# Top.net
KiCad netlist of a schematic drawn in Altium Designer
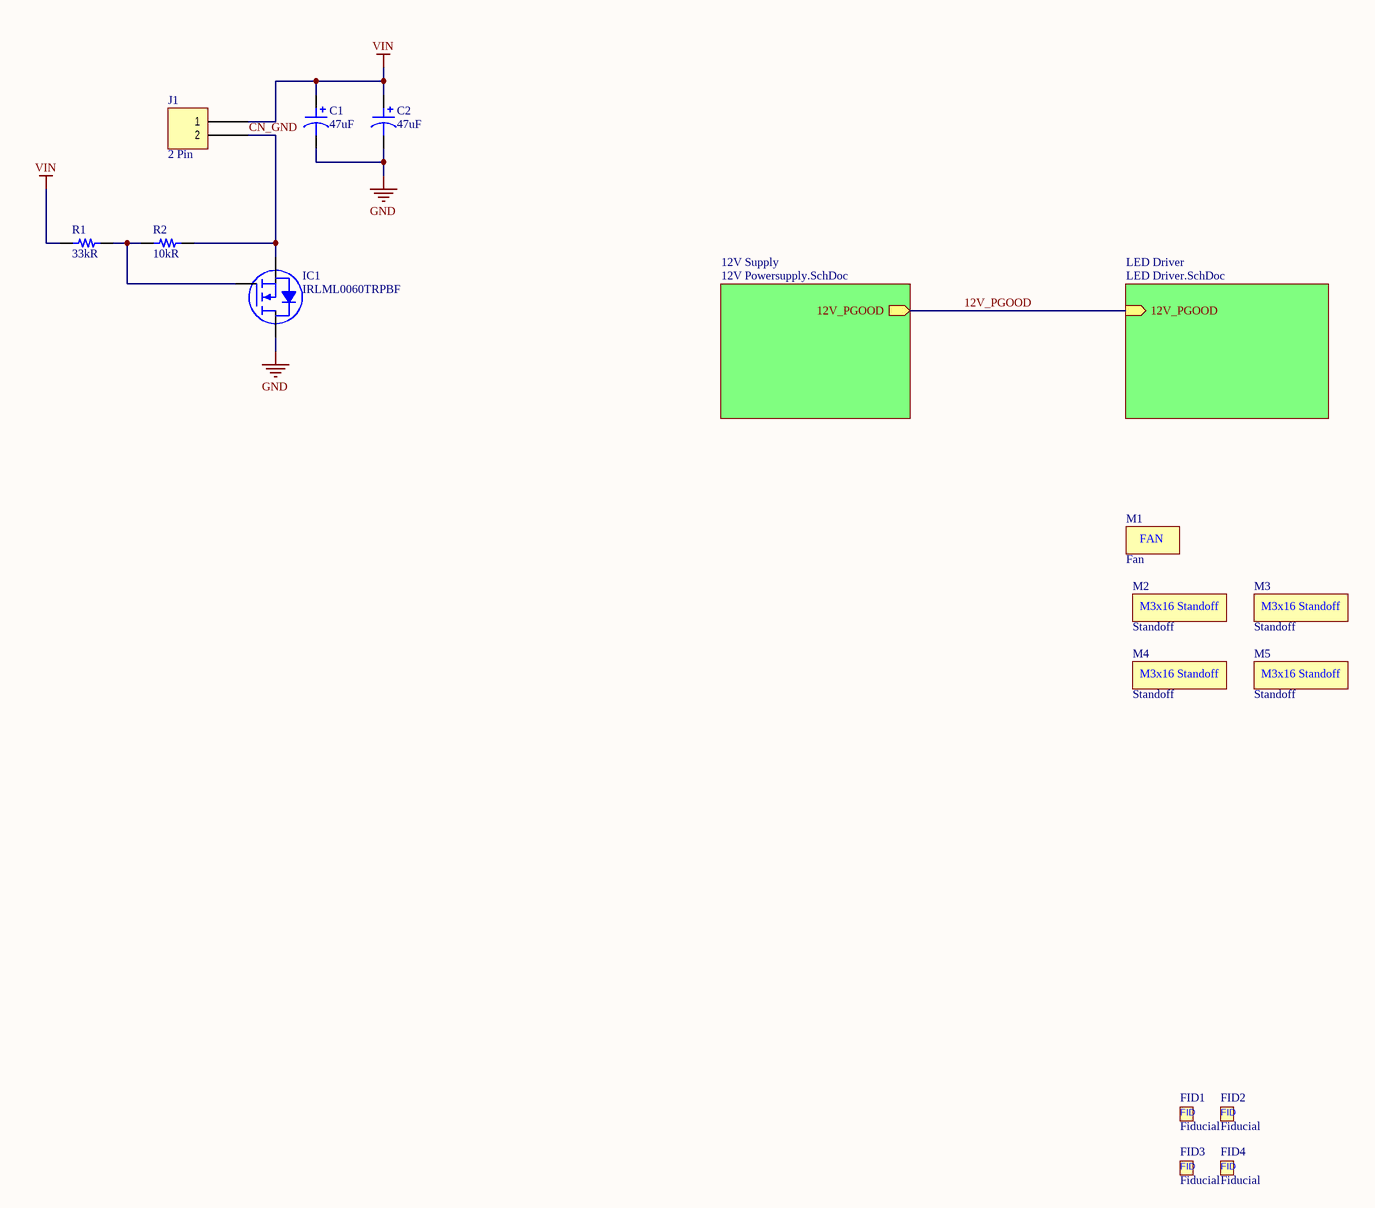
[diagram p0: Top.SchDoc]

(export (version "E")
  (design (tool "Eeschema 10.0.6"))
  (components
    (comp (ref "C1")
      (value "47uF")
      (footprint "CAP ALUM 8.3MM")
      (description "Aluminum Electrolytic Capacitors - SMD 63volts 47uF 20% 85C 8X10")
      (fields (field (name "TOLERANCE") "20%"))
      (libsource (lib "SCH - PASSIVES - POLARISED CAPACITOR") (part "Polarised Capacitor"))
    )
    (comp (ref "C2")
      (value "47uF")
      (footprint "CAP ALUM 8.3MM")
      (description "Aluminum Electrolytic Capacitors - SMD 63volts 47uF 20% 85C 8X10")
      (fields (field (name "TOLERANCE") "20%"))
      (libsource (lib "SCH - PASSIVES - POLARISED CAPACITOR") (part "Polarised Capacitor"))
    )
    (comp (ref "FID1") (value "Fiducial") (footprint "Fiducial") (libsource (lib "Useful") (part "Fiducial")))
    (comp (ref "FID2") (value "Fiducial") (footprint "Fiducial") (libsource (lib "Useful") (part "Fiducial")))
    (comp (ref "FID3") (value "Fiducial") (footprint "Fiducial") (libsource (lib "Useful") (part "Fiducial")))
    (comp (ref "FID4") (value "Fiducial") (footprint "Fiducial") (libsource (lib "Useful") (part "Fiducial")))
    (comp (ref "IC1")
      (value "IRLML0060TRPBF")
      (footprint "INFINEON SOT-23-3")
      (description "MOSFET MOSFT 60V 2.7A 92mOhm 2.5nC Qg")
      (libsource (lib "SCH - FET - N-CH - INFINEON MOSFET N-CH SOT-23-3 GSD") (part "INFINEON MOSFET N-CH SOT-23-3 GSD"))
    )
    (comp (ref "J1")
      (value "2 Pin")
      (footprint "FCI 06-381-2PIN")
      (description "TERM BLOCK HDR 2POS 90DEG 3.81MM")
      (libsource (lib "SCH - CONNECTORS - 2 PIN") (part "2 Pin"))
    )
    (comp (ref "M1")
      (value "Fan")
      (footprint "40MM Fan")
      (description "FAN AXIAL 40X40X15MM 12V WIRE")
      (libsource (lib "Useful") (part "Fan"))
    )
    (comp (ref "M2")
      (value "Standoff")
      (footprint "M3x12.7 M-F Standoff")
      (description "HEX STANDOFF M3 NYLON 1/2")
      (libsource (lib "Useful") (part "Standoff"))
    )
    (comp (ref "M3")
      (value "Standoff")
      (footprint "M3x12.7 M-F Standoff")
      (description "HEX STANDOFF M3 NYLON 1/2")
      (libsource (lib "Useful") (part "Standoff"))
    )
    (comp (ref "M4")
      (value "Standoff")
      (footprint "M3x12.7 M-F Standoff")
      (description "HEX STANDOFF M3 NYLON 1/2")
      (libsource (lib "Useful") (part "Standoff"))
    )
    (comp (ref "M5")
      (value "Standoff")
      (footprint "M3x12.7 M-F Standoff")
      (description "HEX STANDOFF M3 NYLON 1/2")
      (libsource (lib "Useful") (part "Standoff"))
    )
    (comp (ref "R1")
      (value "33kR")
      (footprint "RES 0402/1005")
      (description "RES SMD 33K OHM 5% 1/16W 0402")
      (fields (field (name "TOLERANCE") "5%"))
      (libsource (lib "SCH - PASSIVES - RESISTOR") (part "Resistor"))
    )
    (comp (ref "R2")
      (value "10kR")
      (footprint "RES 0402/1005")
      (description "RES SMD 10K OHM 5% 1/16W 0402")
      (fields (field (name "TOLERANCE") "5%"))
      (libsource (lib "SCH - PASSIVES - RESISTOR") (part "Resistor"))
    )
  )
  (nets
    (net (code "2") (name "/CN_GND") (class "Default")
      (node (ref "IC1") (pin "2") (pinfunction "S_2") (pintype "passive"))
      (node (ref "J1") (pin "2") (pinfunction "2_2") (pintype "passive"))
      (node (ref "R2") (pin "2") (pinfunction "2_2") (pintype "passive"))
    )
    (net (code "3") (name "GND") (class "Default")
      (node (ref "C1") (pin "2") (pinfunction "2_2") (pintype "passive"))
      (node (ref "C2") (pin "2") (pinfunction "2_2") (pintype "passive"))
      (node (ref "IC1") (pin "3") (pinfunction "D_3") (pintype "passive"))
    )
    (net (code "4") (name "Net-(IC1-G)") (class "Default")
      (node (ref "IC1") (pin "1") (pinfunction "G_1") (pintype "passive"))
      (node (ref "R1") (pin "1") (pinfunction "1_1") (pintype "passive"))
      (node (ref "R2") (pin "1") (pinfunction "1_1") (pintype "passive"))
    )
    (net (code "5") (name "VIN") (class "Default")
      (node (ref "C1") (pin "1") (pinfunction "1_1") (pintype "passive"))
      (node (ref "C2") (pin "1") (pinfunction "1_1") (pintype "passive"))
      (node (ref "J1") (pin "1") (pinfunction "1_1") (pintype "passive"))
      (node (ref "R1") (pin "2") (pinfunction "2_2") (pintype "passive"))
    )
  )
)
